# AIRES_MEGA.net
KiCad netlist of a schematic drawn in EAGLE
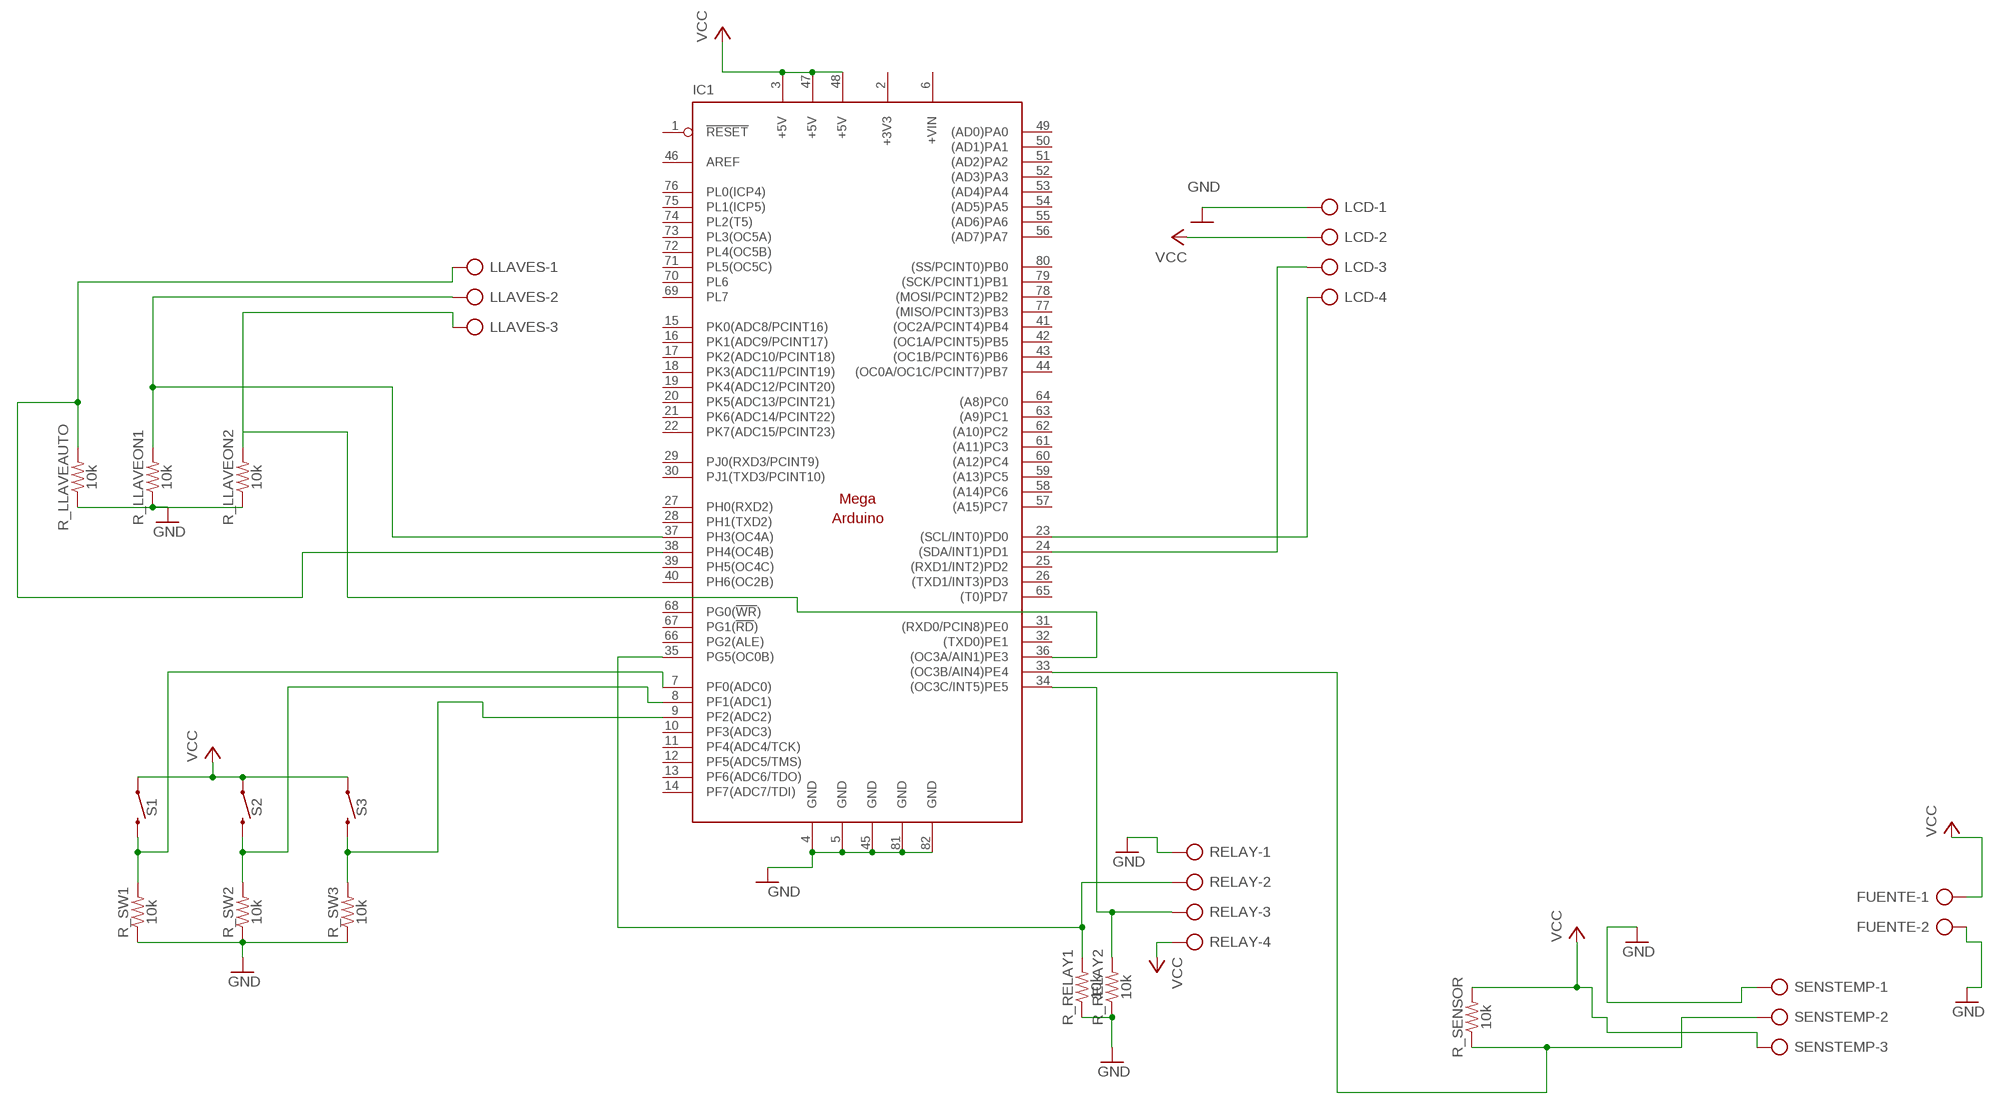
[diagram p0: schematic, sheet 1]

(export (version "E")
  (design (tool "Eeschema 10.0.6"))
  (components
    (comp (ref "FUENTE")
      (value "AK500/2")
      (footprint "eagle-import:AK500_2")
      (libsource (lib "eagle-import") (part "AK500/2"))
    )
    (comp (ref "IC1")
      (value "MEGAARDUINO_1")
      (footprint "eagle-import:MEGA_ARDUINO")
      (libsource (lib "eagle-import") (part "MEGAARDUINO_1"))
    )
    (comp (ref "LCD")
      (value "AK500/4")
      (footprint "eagle-import:AK500_4")
      (libsource (lib "eagle-import") (part "AK500/4"))
    )
    (comp (ref "LLAVES")
      (value "AK500/3")
      (footprint "eagle-import:AK500_3")
      (libsource (lib "eagle-import") (part "AK500/3"))
    )
    (comp (ref "RELAY")
      (value "AK500/4")
      (footprint "eagle-import:AK500_4")
      (libsource (lib "eagle-import") (part "AK500/4"))
    )
    (comp (ref "R_LLAVEAUTO")
      (value "10k")
      (footprint "eagle-import:AXIAL-0.3")
      (libsource (lib "eagle-import") (part "10KOHM-HORIZ-1/4W-1%"))
    )
    (comp (ref "R_LLAVEON1")
      (value "10k")
      (footprint "eagle-import:AXIAL-0.3")
      (libsource (lib "eagle-import") (part "10KOHM-HORIZ-1/4W-1%"))
    )
    (comp (ref "R_LLAVEON2")
      (value "10k")
      (footprint "eagle-import:AXIAL-0.3")
      (libsource (lib "eagle-import") (part "10KOHM-HORIZ-1/4W-1%"))
    )
    (comp (ref "R_RELAY1")
      (value "10k")
      (footprint "eagle-import:AXIAL-0.3")
      (libsource (lib "eagle-import") (part "10KOHM-HORIZ-1/4W-1%"))
    )
    (comp (ref "R_RELAY2")
      (value "10k")
      (footprint "eagle-import:AXIAL-0.3")
      (libsource (lib "eagle-import") (part "10KOHM-HORIZ-1/4W-1%"))
    )
    (comp (ref "R_SENSOR")
      (value "10k")
      (footprint "eagle-import:AXIAL-0.3")
      (libsource (lib "eagle-import") (part "10KOHM-HORIZ-1/4W-1%"))
    )
    (comp (ref "R_SW1")
      (value "10k")
      (footprint "eagle-import:AXIAL-0.3")
      (libsource (lib "eagle-import") (part "10KOHM-HORIZ-1/4W-1%"))
    )
    (comp (ref "R_SW2")
      (value "10k")
      (footprint "eagle-import:AXIAL-0.3")
      (libsource (lib "eagle-import") (part "10KOHM-HORIZ-1/4W-1%"))
    )
    (comp (ref "R_SW3")
      (value "10k")
      (footprint "eagle-import:AXIAL-0.3")
      (libsource (lib "eagle-import") (part "10KOHM-HORIZ-1/4W-1%"))
    )
    (comp (ref "S1")
      (value "MOMENTARY-SWITCH-SPST-PTH-12MM")
      (footprint "eagle-import:TACTILE_SWITCH_PTH_12MM")
      (libsource (lib "eagle-import") (part "MOMENTARY-SWITCH-SPST-PTH-12MM"))
    )
    (comp (ref "S2")
      (value "MOMENTARY-SWITCH-SPST-PTH-12MM")
      (footprint "eagle-import:TACTILE_SWITCH_PTH_12MM")
      (libsource (lib "eagle-import") (part "MOMENTARY-SWITCH-SPST-PTH-12MM"))
    )
    (comp (ref "S3")
      (value "MOMENTARY-SWITCH-SPST-PTH-12MM")
      (footprint "eagle-import:TACTILE_SWITCH_PTH_12MM")
      (libsource (lib "eagle-import") (part "MOMENTARY-SWITCH-SPST-PTH-12MM"))
    )
    (comp (ref "SENSTEMP")
      (value "AK500/3")
      (footprint "eagle-import:AK500_3")
      (libsource (lib "eagle-import") (part "AK500/3"))
    )
  )
  (nets
    (net (code "1") (name "/+3V3") (class "Default")
      (node (ref "IC1") (pin "2") (pinfunction "+3V3_2") (pintype "power_in"))
    )
    (net (code "2") (name "/+VIN") (class "Default")
      (node (ref "IC1") (pin "6") (pinfunction "+VIN_6") (pintype "power_in"))
    )
    (net (code "3") (name "GND") (class "Default")
      (node (ref "FUENTE") (pin "2") (pinfunction "KL_2") (pintype "passive"))
      (node (ref "IC1") (pin "4") (pinfunction "GND_4") (pintype "power_in"))
      (node (ref "IC1") (pin "45") (pinfunction "GND_45") (pintype "power_in"))
      (node (ref "IC1") (pin "5") (pinfunction "GND_5") (pintype "power_in"))
      (node (ref "IC1") (pin "81") (pinfunction "GND_81") (pintype "power_in"))
      (node (ref "IC1") (pin "82") (pinfunction "GND_82") (pintype "power_in"))
      (node (ref "LCD") (pin "1") (pinfunction "KL_1") (pintype "passive"))
      (node (ref "RELAY") (pin "1") (pinfunction "KL_1") (pintype "passive"))
      (node (ref "R_LLAVEAUTO") (pin "P$1") (pinfunction "1_P$1") (pintype "passive"))
      (node (ref "R_LLAVEON1") (pin "P$1") (pinfunction "1_P$1") (pintype "passive"))
      (node (ref "R_LLAVEON2") (pin "P$1") (pinfunction "1_P$1") (pintype "passive"))
      (node (ref "R_RELAY1") (pin "P$1") (pinfunction "1_P$1") (pintype "passive"))
      (node (ref "R_RELAY2") (pin "P$1") (pinfunction "1_P$1") (pintype "passive"))
      (node (ref "R_SW1") (pin "P$1") (pinfunction "1_P$1") (pintype "passive"))
      (node (ref "R_SW2") (pin "P$1") (pinfunction "1_P$1") (pintype "passive"))
      (node (ref "R_SW3") (pin "P$1") (pinfunction "1_P$1") (pintype "passive"))
      (node (ref "SENSTEMP") (pin "1") (pinfunction "KL_1") (pintype "passive"))
    )
    (net (code "4") (name "Net-(IC1-(OC3A{slash}AIN1)PE3)") (class "Default")
      (node (ref "IC1") (pin "36") (pinfunction "(OC3A/AIN1)PE3_36") (pintype "bidirectional"))
      (node (ref "LLAVES") (pin "3") (pinfunction "KL_3") (pintype "passive"))
      (node (ref "R_LLAVEON2") (pin "P$2") (pinfunction "2_P$2") (pintype "passive"))
    )
    (net (code "5") (name "Net-(IC1-(OC3B{slash}AIN4)PE4)") (class "Default")
      (node (ref "IC1") (pin "33") (pinfunction "(OC3B/AIN4)PE4_33") (pintype "bidirectional"))
      (node (ref "R_SENSOR") (pin "P$1") (pinfunction "1_P$1") (pintype "passive"))
      (node (ref "SENSTEMP") (pin "2") (pinfunction "KL_2") (pintype "passive"))
    )
    (net (code "6") (name "Net-(IC1-(OC3C{slash}INT5)PE5)") (class "Default")
      (node (ref "IC1") (pin "34") (pinfunction "(OC3C/INT5)PE5_34") (pintype "bidirectional"))
      (node (ref "RELAY") (pin "3") (pinfunction "KL_3") (pintype "passive"))
      (node (ref "R_RELAY2") (pin "P$2") (pinfunction "2_P$2") (pintype "passive"))
    )
    (net (code "7") (name "Net-(IC1-(SCL{slash}INT0)PD0)") (class "Default")
      (node (ref "IC1") (pin "23") (pinfunction "(SCL/INT0)PD0_23") (pintype "bidirectional"))
      (node (ref "LCD") (pin "4") (pinfunction "KL_4") (pintype "passive"))
    )
    (net (code "8") (name "Net-(IC1-(SDA{slash}INT1)PD1)") (class "Default")
      (node (ref "IC1") (pin "24") (pinfunction "(SDA/INT1)PD1_24") (pintype "bidirectional"))
      (node (ref "LCD") (pin "3") (pinfunction "KL_3") (pintype "passive"))
    )
    (net (code "9") (name "Net-(IC1-PF0(ADC0))") (class "Default")
      (node (ref "IC1") (pin "7") (pinfunction "PF0(ADC0)_7") (pintype "bidirectional"))
      (node (ref "R_SW1") (pin "P$2") (pinfunction "2_P$2") (pintype "passive"))
      (node (ref "S1") (pin "3") (pinfunction "2_3") (pintype "passive"))
    )
    (net (code "10") (name "Net-(IC1-PF1(ADC1))") (class "Default")
      (node (ref "IC1") (pin "8") (pinfunction "PF1(ADC1)_8") (pintype "bidirectional"))
      (node (ref "R_SW2") (pin "P$2") (pinfunction "2_P$2") (pintype "passive"))
      (node (ref "S2") (pin "3") (pinfunction "2_3") (pintype "passive"))
    )
    (net (code "11") (name "Net-(IC1-PF2(ADC2))") (class "Default")
      (node (ref "IC1") (pin "9") (pinfunction "PF2(ADC2)_9") (pintype "bidirectional"))
      (node (ref "R_SW3") (pin "P$2") (pinfunction "2_P$2") (pintype "passive"))
      (node (ref "S3") (pin "3") (pinfunction "2_3") (pintype "passive"))
    )
    (net (code "12") (name "Net-(IC1-PG5(OC0B))") (class "Default")
      (node (ref "IC1") (pin "35") (pinfunction "PG5(OC0B)_35") (pintype "bidirectional"))
      (node (ref "RELAY") (pin "2") (pinfunction "KL_2") (pintype "passive"))
      (node (ref "R_RELAY1") (pin "P$2") (pinfunction "2_P$2") (pintype "passive"))
    )
    (net (code "13") (name "Net-(IC1-PH3(OC4A))") (class "Default")
      (node (ref "IC1") (pin "37") (pinfunction "PH3(OC4A)_37") (pintype "bidirectional"))
      (node (ref "LLAVES") (pin "2") (pinfunction "KL_2") (pintype "passive"))
      (node (ref "R_LLAVEON1") (pin "P$2") (pinfunction "2_P$2") (pintype "passive"))
    )
    (net (code "14") (name "Net-(IC1-PH4(OC4B))") (class "Default")
      (node (ref "IC1") (pin "38") (pinfunction "PH4(OC4B)_38") (pintype "bidirectional"))
      (node (ref "LLAVES") (pin "1") (pinfunction "KL_1") (pintype "passive"))
      (node (ref "R_LLAVEAUTO") (pin "P$2") (pinfunction "2_P$2") (pintype "passive"))
    )
    (net (code "15") (name "VCC") (class "Default")
      (node (ref "FUENTE") (pin "1") (pinfunction "KL_1") (pintype "passive"))
      (node (ref "IC1") (pin "3") (pinfunction "+5V_3") (pintype "power_in"))
      (node (ref "IC1") (pin "47") (pinfunction "+5V_47") (pintype "power_in"))
      (node (ref "IC1") (pin "48") (pinfunction "+5V_48") (pintype "power_in"))
      (node (ref "LCD") (pin "2") (pinfunction "KL_2") (pintype "passive"))
      (node (ref "RELAY") (pin "4") (pinfunction "KL_4") (pintype "passive"))
      (node (ref "R_SENSOR") (pin "P$2") (pinfunction "2_P$2") (pintype "passive"))
      (node (ref "S1") (pin "1") (pinfunction "1_1") (pintype "passive"))
      (node (ref "S2") (pin "1") (pinfunction "1_1") (pintype "passive"))
      (node (ref "S3") (pin "1") (pinfunction "1_1") (pintype "passive"))
      (node (ref "SENSTEMP") (pin "3") (pinfunction "KL_3") (pintype "passive"))
    )
    (net (code "16") (name "unconnected-(IC1-(A8)PC0-Pad64)") (class "Default")
      (node (ref "IC1") (pin "64") (pinfunction "(A8)PC0_64") (pintype "bidirectional"))
    )
    (net (code "17") (name "unconnected-(IC1-(A9)PC1-Pad63)") (class "Default")
      (node (ref "IC1") (pin "63") (pinfunction "(A9)PC1_63") (pintype "bidirectional"))
    )
    (net (code "18") (name "unconnected-(IC1-(A10)PC2-Pad62)") (class "Default")
      (node (ref "IC1") (pin "62") (pinfunction "(A10)PC2_62") (pintype "bidirectional"))
    )
    (net (code "19") (name "unconnected-(IC1-(A11)PC3-Pad61)") (class "Default")
      (node (ref "IC1") (pin "61") (pinfunction "(A11)PC3_61") (pintype "bidirectional"))
    )
    (net (code "20") (name "unconnected-(IC1-(A12)PC4-Pad60)") (class "Default")
      (node (ref "IC1") (pin "60") (pinfunction "(A12)PC4_60") (pintype "bidirectional"))
    )
    (net (code "21") (name "unconnected-(IC1-(A13)PC5-Pad59)") (class "Default")
      (node (ref "IC1") (pin "59") (pinfunction "(A13)PC5_59") (pintype "bidirectional"))
    )
    (net (code "22") (name "unconnected-(IC1-(A14)PC6-Pad58)") (class "Default")
      (node (ref "IC1") (pin "58") (pinfunction "(A14)PC6_58") (pintype "bidirectional"))
    )
    (net (code "23") (name "unconnected-(IC1-(A15)PC7-Pad57)") (class "Default")
      (node (ref "IC1") (pin "57") (pinfunction "(A15)PC7_57") (pintype "bidirectional"))
    )
    (net (code "24") (name "unconnected-(IC1-(AD0)PA0-Pad49)") (class "Default")
      (node (ref "IC1") (pin "49") (pinfunction "(AD0)PA0_49") (pintype "bidirectional"))
    )
    (net (code "25") (name "unconnected-(IC1-(AD1)PA1-Pad50)") (class "Default")
      (node (ref "IC1") (pin "50") (pinfunction "(AD1)PA1_50") (pintype "bidirectional"))
    )
    (net (code "26") (name "unconnected-(IC1-(AD2)PA2-Pad51)") (class "Default")
      (node (ref "IC1") (pin "51") (pinfunction "(AD2)PA2_51") (pintype "bidirectional"))
    )
    (net (code "27") (name "unconnected-(IC1-(AD3)PA3-Pad52)") (class "Default")
      (node (ref "IC1") (pin "52") (pinfunction "(AD3)PA3_52") (pintype "bidirectional"))
    )
    (net (code "28") (name "unconnected-(IC1-(AD4)PA4-Pad53)") (class "Default")
      (node (ref "IC1") (pin "53") (pinfunction "(AD4)PA4_53") (pintype "bidirectional"))
    )
    (net (code "29") (name "unconnected-(IC1-(AD5)PA5-Pad54)") (class "Default")
      (node (ref "IC1") (pin "54") (pinfunction "(AD5)PA5_54") (pintype "bidirectional"))
    )
    (net (code "30") (name "unconnected-(IC1-(AD6)PA6-Pad55)") (class "Default")
      (node (ref "IC1") (pin "55") (pinfunction "(AD6)PA6_55") (pintype "bidirectional"))
    )
    (net (code "31") (name "unconnected-(IC1-(AD7)PA7-Pad56)") (class "Default")
      (node (ref "IC1") (pin "56") (pinfunction "(AD7)PA7_56") (pintype "bidirectional"))
    )
    (net (code "32") (name "unconnected-(IC1-(MISO{slash}PCINT3)PB3-Pad77)") (class "Default")
      (node (ref "IC1") (pin "77") (pinfunction "(MISO/PCINT3)PB3_77") (pintype "bidirectional"))
    )
    (net (code "33") (name "unconnected-(IC1-(MOSI{slash}PCINT2)PB2-Pad78)") (class "Default")
      (node (ref "IC1") (pin "78") (pinfunction "(MOSI/PCINT2)PB2_78") (pintype "bidirectional"))
    )
    (net (code "34") (name "unconnected-(IC1-(OC0A{slash}OC1C{slash}PCINT7)PB7-Pad44)") (class "Default")
      (node (ref "IC1") (pin "44") (pinfunction "(OC0A/OC1C/PCINT7)PB7_44") (pintype "bidirectional"))
    )
    (net (code "35") (name "unconnected-(IC1-(OC1A{slash}PCINT5)PB5-Pad42)") (class "Default")
      (node (ref "IC1") (pin "42") (pinfunction "(OC1A/PCINT5)PB5_42") (pintype "bidirectional"))
    )
    (net (code "36") (name "unconnected-(IC1-(OC1B{slash}PCINT6)PB6-Pad43)") (class "Default")
      (node (ref "IC1") (pin "43") (pinfunction "(OC1B/PCINT6)PB6_43") (pintype "bidirectional"))
    )
    (net (code "37") (name "unconnected-(IC1-(OC2A{slash}PCINT4)PB4-Pad41)") (class "Default")
      (node (ref "IC1") (pin "41") (pinfunction "(OC2A/PCINT4)PB4_41") (pintype "bidirectional"))
    )
    (net (code "38") (name "unconnected-(IC1-(RXD0{slash}PCIN8)PE0-Pad31)") (class "Default")
      (node (ref "IC1") (pin "31") (pinfunction "(RXD0/PCIN8)PE0_31") (pintype "bidirectional"))
    )
    (net (code "39") (name "unconnected-(IC1-(RXD1{slash}INT2)PD2-Pad25)") (class "Default")
      (node (ref "IC1") (pin "25") (pinfunction "(RXD1/INT2)PD2_25") (pintype "bidirectional"))
    )
    (net (code "40") (name "unconnected-(IC1-(SCK{slash}PCINT1)PB1-Pad79)") (class "Default")
      (node (ref "IC1") (pin "79") (pinfunction "(SCK/PCINT1)PB1_79") (pintype "bidirectional"))
    )
    (net (code "41") (name "unconnected-(IC1-(SS{slash}PCINT0)PB0-Pad80)") (class "Default")
      (node (ref "IC1") (pin "80") (pinfunction "(SS/PCINT0)PB0_80") (pintype "bidirectional"))
    )
    (net (code "42") (name "unconnected-(IC1-(T0)PD7-Pad65)") (class "Default")
      (node (ref "IC1") (pin "65") (pinfunction "(T0)PD7_65") (pintype "bidirectional"))
    )
    (net (code "43") (name "unconnected-(IC1-(TXD0)PE1-Pad32)") (class "Default")
      (node (ref "IC1") (pin "32") (pinfunction "(TXD0)PE1_32") (pintype "bidirectional"))
    )
    (net (code "44") (name "unconnected-(IC1-(TXD1{slash}INT3)PD3-Pad26)") (class "Default")
      (node (ref "IC1") (pin "26") (pinfunction "(TXD1/INT3)PD3_26") (pintype "bidirectional"))
    )
    (net (code "45") (name "unconnected-(IC1-AREF-Pad46)") (class "Default")
      (node (ref "IC1") (pin "46") (pinfunction "AREF_46") (pintype "bidirectional"))
    )
    (net (code "46") (name "unconnected-(IC1-PF3(ADC3)-Pad10)") (class "Default")
      (node (ref "IC1") (pin "10") (pinfunction "PF3(ADC3)_10") (pintype "bidirectional"))
    )
    (net (code "47") (name "unconnected-(IC1-PF4(ADC4{slash}TCK)-Pad11)") (class "Default")
      (node (ref "IC1") (pin "11") (pinfunction "PF4(ADC4/TCK)_11") (pintype "bidirectional"))
    )
    (net (code "48") (name "unconnected-(IC1-PF5(ADC5{slash}TMS)-Pad12)") (class "Default")
      (node (ref "IC1") (pin "12") (pinfunction "PF5(ADC5/TMS)_12") (pintype "bidirectional"))
    )
    (net (code "49") (name "unconnected-(IC1-PF6(ADC6{slash}TDO)-Pad13)") (class "Default")
      (node (ref "IC1") (pin "13") (pinfunction "PF6(ADC6/TDO)_13") (pintype "bidirectional"))
    )
    (net (code "50") (name "unconnected-(IC1-PF7(ADC7{slash}TDI)-Pad14)") (class "Default")
      (node (ref "IC1") (pin "14") (pinfunction "PF7(ADC7/TDI)_14") (pintype "bidirectional"))
    )
    (net (code "51") (name "unconnected-(IC1-PG0(~{WR})-Pad68)") (class "Default")
      (node (ref "IC1") (pin "68") (pinfunction "PG0(~{WR})_68") (pintype "bidirectional"))
    )
    (net (code "52") (name "unconnected-(IC1-PG1(~{RD})-Pad67)") (class "Default")
      (node (ref "IC1") (pin "67") (pinfunction "PG1(~{RD})_67") (pintype "bidirectional"))
    )
    (net (code "53") (name "unconnected-(IC1-PG2(ALE)-Pad66)") (class "Default")
      (node (ref "IC1") (pin "66") (pinfunction "PG2(ALE)_66") (pintype "bidirectional"))
    )
    (net (code "54") (name "unconnected-(IC1-PH0(RXD2)-Pad27)") (class "Default")
      (node (ref "IC1") (pin "27") (pinfunction "PH0(RXD2)_27") (pintype "bidirectional"))
    )
    (net (code "55") (name "unconnected-(IC1-PH1(TXD2)-Pad28)") (class "Default")
      (node (ref "IC1") (pin "28") (pinfunction "PH1(TXD2)_28") (pintype "bidirectional"))
    )
    (net (code "56") (name "unconnected-(IC1-PH5(OC4C)-Pad39)") (class "Default")
      (node (ref "IC1") (pin "39") (pinfunction "PH5(OC4C)_39") (pintype "bidirectional"))
    )
    (net (code "57") (name "unconnected-(IC1-PH6(OC2B)-Pad40)") (class "Default")
      (node (ref "IC1") (pin "40") (pinfunction "PH6(OC2B)_40") (pintype "bidirectional"))
    )
    (net (code "58") (name "unconnected-(IC1-PJ0(RXD3{slash}PCINT9)-Pad29)") (class "Default")
      (node (ref "IC1") (pin "29") (pinfunction "PJ0(RXD3/PCINT9)_29") (pintype "bidirectional"))
    )
    (net (code "59") (name "unconnected-(IC1-PJ1(TXD3{slash}PCINT10)-Pad30)") (class "Default")
      (node (ref "IC1") (pin "30") (pinfunction "PJ1(TXD3/PCINT10)_30") (pintype "bidirectional"))
    )
    (net (code "60") (name "unconnected-(IC1-PK0(ADC8{slash}PCINT16)-Pad15)") (class "Default")
      (node (ref "IC1") (pin "15") (pinfunction "PK0(ADC8/PCINT16)_15") (pintype "bidirectional"))
    )
    (net (code "61") (name "unconnected-(IC1-PK1(ADC9{slash}PCINT17)-Pad16)") (class "Default")
      (node (ref "IC1") (pin "16") (pinfunction "PK1(ADC9/PCINT17)_16") (pintype "bidirectional"))
    )
    (net (code "62") (name "unconnected-(IC1-PK2(ADC10{slash}PCINT18)-Pad17)") (class "Default")
      (node (ref "IC1") (pin "17") (pinfunction "PK2(ADC10/PCINT18)_17") (pintype "bidirectional"))
    )
    (net (code "63") (name "unconnected-(IC1-PK3(ADC11{slash}PCINT19)-Pad18)") (class "Default")
      (node (ref "IC1") (pin "18") (pinfunction "PK3(ADC11/PCINT19)_18") (pintype "bidirectional"))
    )
    (net (code "64") (name "unconnected-(IC1-PK4(ADC12{slash}PCINT20)-Pad19)") (class "Default")
      (node (ref "IC1") (pin "19") (pinfunction "PK4(ADC12/PCINT20)_19") (pintype "bidirectional"))
    )
    (net (code "65") (name "unconnected-(IC1-PK5(ADC13{slash}PCINT21)-Pad20)") (class "Default")
      (node (ref "IC1") (pin "20") (pinfunction "PK5(ADC13/PCINT21)_20") (pintype "bidirectional"))
    )
    (net (code "66") (name "unconnected-(IC1-PK6(ADC14{slash}PCINT22)-Pad21)") (class "Default")
      (node (ref "IC1") (pin "21") (pinfunction "PK6(ADC14/PCINT22)_21") (pintype "bidirectional"))
    )
    (net (code "67") (name "unconnected-(IC1-PK7(ADC15{slash}PCINT23)-Pad22)") (class "Default")
      (node (ref "IC1") (pin "22") (pinfunction "PK7(ADC15/PCINT23)_22") (pintype "bidirectional"))
    )
    (net (code "68") (name "unconnected-(IC1-PL0(ICP4)-Pad76)") (class "Default")
      (node (ref "IC1") (pin "76") (pinfunction "PL0(ICP4)_76") (pintype "bidirectional"))
    )
    (net (code "69") (name "unconnected-(IC1-PL1(ICP5)-Pad75)") (class "Default")
      (node (ref "IC1") (pin "75") (pinfunction "PL1(ICP5)_75") (pintype "bidirectional"))
    )
    (net (code "70") (name "unconnected-(IC1-PL2(T5)-Pad74)") (class "Default")
      (node (ref "IC1") (pin "74") (pinfunction "PL2(T5)_74") (pintype "bidirectional"))
    )
    (net (code "71") (name "unconnected-(IC1-PL3(OC5A)-Pad73)") (class "Default")
      (node (ref "IC1") (pin "73") (pinfunction "PL3(OC5A)_73") (pintype "bidirectional"))
    )
    (net (code "72") (name "unconnected-(IC1-PL4(OC5B)-Pad72)") (class "Default")
      (node (ref "IC1") (pin "72") (pinfunction "PL4(OC5B)_72") (pintype "bidirectional"))
    )
    (net (code "73") (name "unconnected-(IC1-PL5(OC5C)-Pad71)") (class "Default")
      (node (ref "IC1") (pin "71") (pinfunction "PL5(OC5C)_71") (pintype "bidirectional"))
    )
    (net (code "74") (name "unconnected-(IC1-PL6-Pad70)") (class "Default")
      (node (ref "IC1") (pin "70") (pinfunction "PL6_70") (pintype "bidirectional"))
    )
    (net (code "75") (name "unconnected-(IC1-PL7-Pad69)") (class "Default")
      (node (ref "IC1") (pin "69") (pinfunction "PL7_69") (pintype "bidirectional"))
    )
    (net (code "76") (name "unconnected-(IC1-~{RESET}-Pad1)") (class "Default")
      (node (ref "IC1") (pin "1") (pinfunction "~{RESET}_1") (pintype "bidirectional"))
    )
  )
)
